# AmbaSat-01-SHT3x-DIS.net
KiCad netlist of a schematic drawn in EAGLE
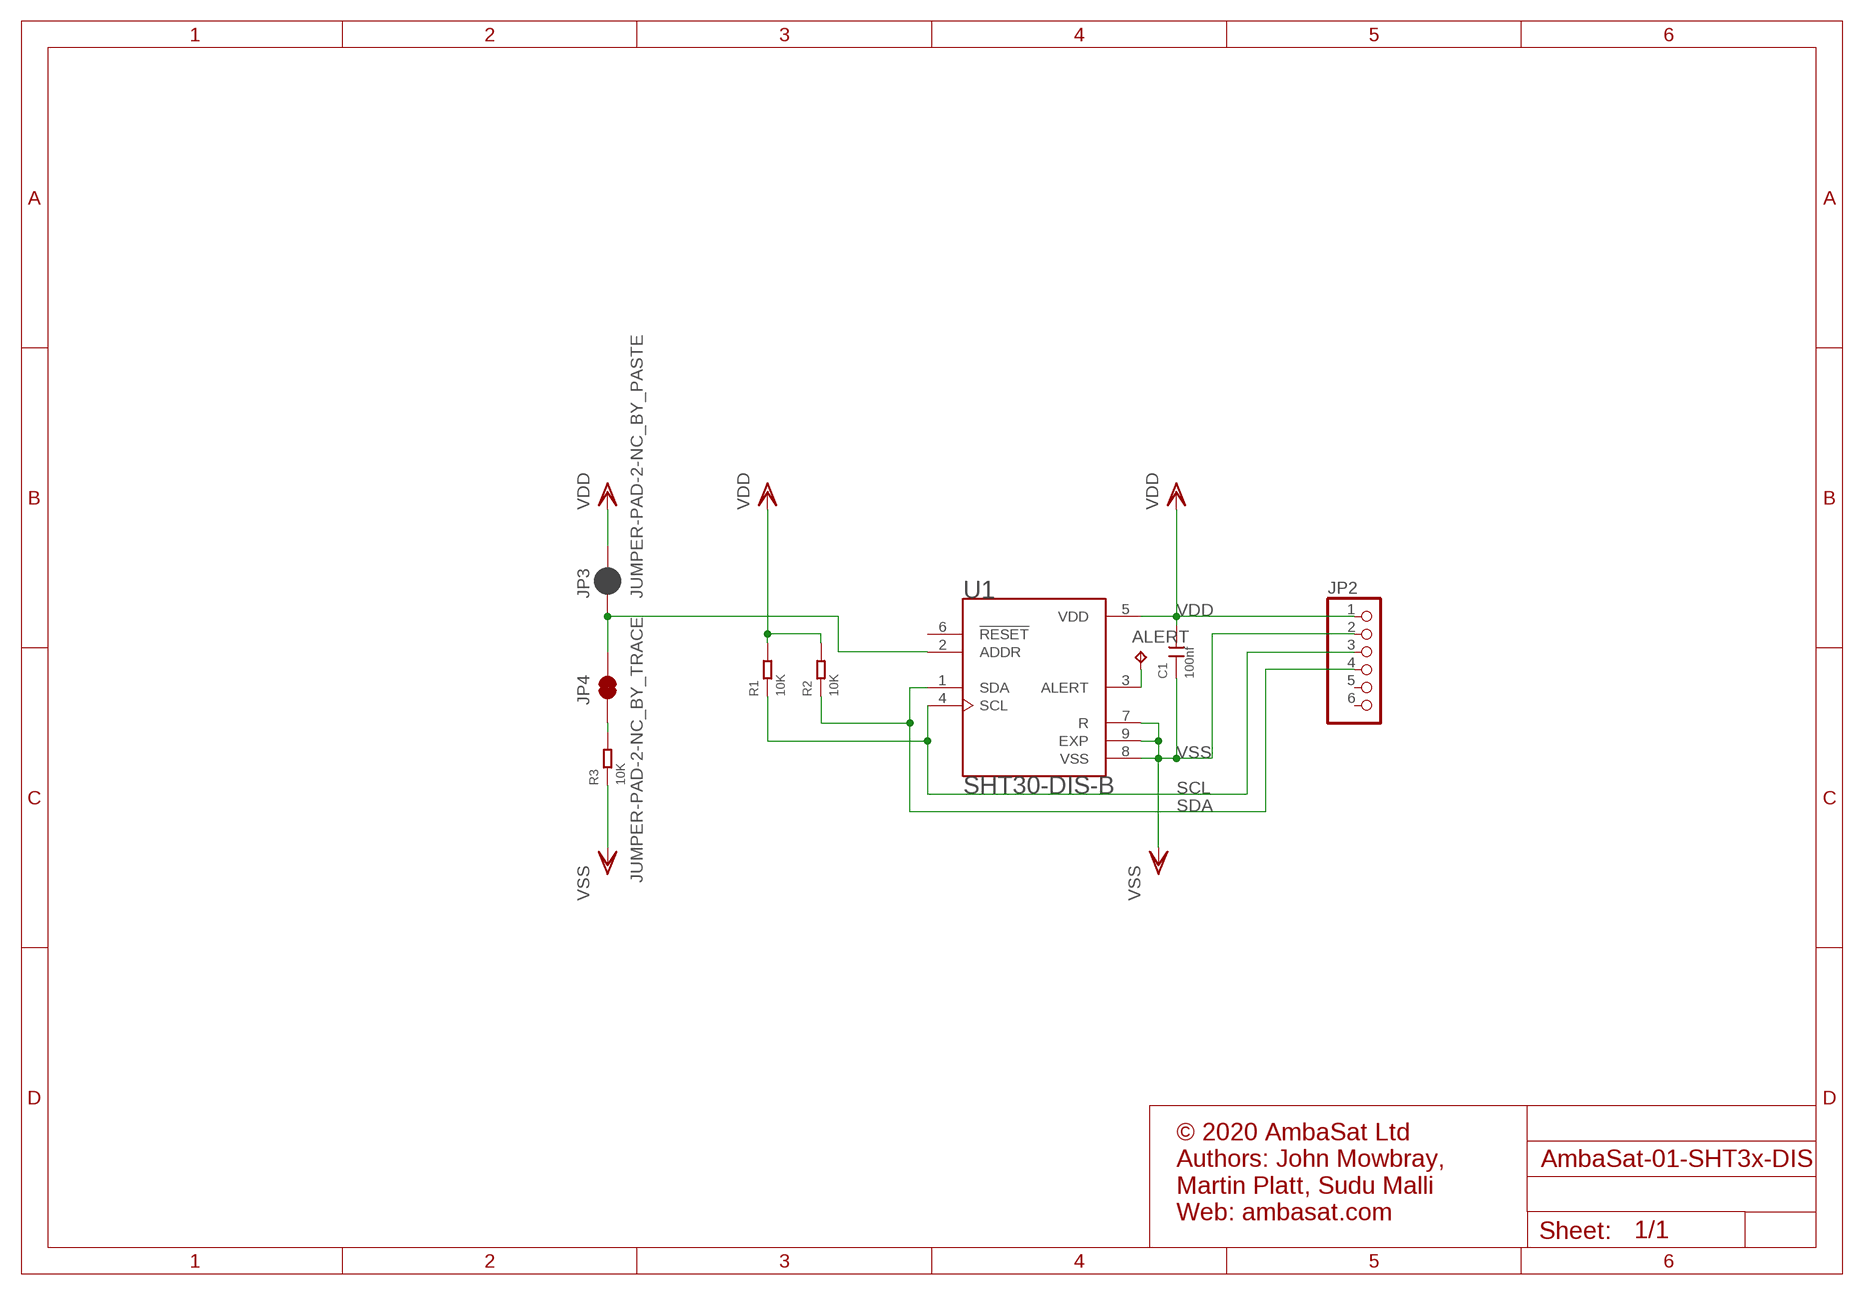
[diagram p0: schematic, sheet 1]

(export (version "E")
  (design (tool "Eeschema 10.0.6"))
  (components
    (comp (ref "ALERT")
      (value "TPTP06R")
      (footprint "eagle-import:TP06R")
      (libsource (lib "eagle-import") (part "TPTP06R"))
    )
    (comp (ref "C1")
      (value "100nf")
      (footprint "eagle-import:C0805")
      (fields (field (name "MPN") "CC0805KRX7R9BB104"))
      (libsource (lib "eagle-import") (part "CERAMIC-100NF-50V-10%-X7R(0805)"))
    )
    (comp (ref "JP2")
      (value "HEADER-1X6")
      (footprint "eagle-import:1X06_OVAL")
      (libsource (lib "eagle-import") (part "HEADER-1X6"))
    )
    (comp (ref "JP3")
      (value "JUMPER-PAD-2-NC_BY_PASTE")
      (footprint "eagle-import:PAD-JUMPER-2-NC_BY_PASTE_YES_SILK")
      (libsource (lib "eagle-import") (part "JUMPER-PAD-2-NC_BY_PASTE"))
    )
    (comp (ref "JP4")
      (value "JUMPER-PAD-2-NC_BY_TRACE")
      (footprint "eagle-import:PAD-JUMPER-2-NC_BY_TRACE_YES_SILK")
      (libsource (lib "eagle-import") (part "JUMPER-PAD-2-NC_BY_TRACE"))
    )
    (comp (ref "R1")
      (value "10K")
      (footprint "eagle-import:R0805")
      (fields (field (name "MPN") "RC0805FR-0710KL"))
      (libsource (lib "eagle-import") (part "SMD-RES-10K-1%-1/8W(0805)"))
    )
    (comp (ref "R2")
      (value "10K")
      (footprint "eagle-import:R0805")
      (fields (field (name "MPN") "RC0805FR-0710KL"))
      (libsource (lib "eagle-import") (part "SMD-RES-10K-1%-1/8W(0805)"))
    )
    (comp (ref "R3")
      (value "10K")
      (footprint "eagle-import:R0805")
      (fields (field (name "MPN") "RC0805FR-0710KL"))
      (libsource (lib "eagle-import") (part "SMD-RES-10K-1%-1/8W(0805)"))
    )
    (comp (ref "U1")
      (value "SHT30-DIS-B")
      (footprint "eagle-import:DFN250X250X100-9N")
      (fields (field (name "MF") "Sensirion AG"))
      (libsource (lib "eagle-import") (part "SHT30-DIS-B"))
    )
  )
  (nets
    (net (code "1") (name "/SCL") (class "Default")
      (node (ref "JP2") (pin "3") (pinfunction "3_3") (pintype "passive"))
      (node (ref "R1") (pin "1") (pinfunction "1_1") (pintype "passive"))
      (node (ref "U1") (pin "4") (pinfunction "SCL_4") (pintype "bidirectional"))
    )
    (net (code "2") (name "/SDA") (class "Default")
      (node (ref "JP2") (pin "4") (pinfunction "4_4") (pintype "passive"))
      (node (ref "R2") (pin "1") (pinfunction "1_1") (pintype "passive"))
      (node (ref "U1") (pin "1") (pinfunction "SDA_1") (pintype "bidirectional"))
    )
    (net (code "3") (name "Net-(JP4-Pad1)") (class "Default")
      (node (ref "JP4") (pin "1") (pinfunction "1_1") (pintype "passive"))
      (node (ref "R3") (pin "2") (pinfunction "2_2") (pintype "passive"))
    )
    (net (code "4") (name "Net-(U1-ADDR)") (class "Default")
      (node (ref "JP3") (pin "1") (pinfunction "1_1") (pintype "passive"))
      (node (ref "JP4") (pin "2") (pinfunction "2_2") (pintype "passive"))
      (node (ref "U1") (pin "2") (pinfunction "ADDR_2") (pintype "input"))
    )
    (net (code "5") (name "Net-(U1-ALERT)") (class "Default")
      (node (ref "ALERT") (pin "TP") (pinfunction "TP_TP") (pintype "input"))
      (node (ref "U1") (pin "3") (pinfunction "ALERT_3") (pintype "output"))
    )
    (net (code "6") (name "VDD") (class "Default")
      (node (ref "C1") (pin "2") (pinfunction "2_2") (pintype "passive"))
      (node (ref "JP2") (pin "1") (pinfunction "1_1") (pintype "passive"))
      (node (ref "JP3") (pin "2") (pinfunction "2_2") (pintype "passive"))
      (node (ref "R1") (pin "2") (pinfunction "2_2") (pintype "passive"))
      (node (ref "R2") (pin "2") (pinfunction "2_2") (pintype "passive"))
      (node (ref "U1") (pin "5") (pinfunction "VDD_5") (pintype "power_in"))
    )
    (net (code "7") (name "VSS") (class "Default")
      (node (ref "C1") (pin "1") (pinfunction "1_1") (pintype "passive"))
      (node (ref "JP2") (pin "2") (pinfunction "2_2") (pintype "passive"))
      (node (ref "R3") (pin "1") (pinfunction "1_1") (pintype "passive"))
      (node (ref "U1") (pin "7") (pinfunction "R_7") (pintype "passive"))
      (node (ref "U1") (pin "8") (pinfunction "VSS_8") (pintype "passive"))
      (node (ref "U1") (pin "9") (pinfunction "EXP_9") (pintype "passive"))
    )
    (net (code "8") (name "unconnected-(JP2-Pad5)") (class "Default")
      (node (ref "JP2") (pin "5") (pinfunction "5_5") (pintype "passive"))
    )
    (net (code "9") (name "unconnected-(JP2-Pad6)") (class "Default")
      (node (ref "JP2") (pin "6") (pinfunction "6_6") (pintype "passive"))
    )
    (net (code "10") (name "unconnected-(U1-~{RESET}-Pad6)") (class "Default")
      (node (ref "U1") (pin "6") (pinfunction "~{RESET}_6") (pintype "input"))
    )
  )
)
